# 3_-_IO_Socket_1.net
KiCad netlist of a schematic drawn in Altium Designer
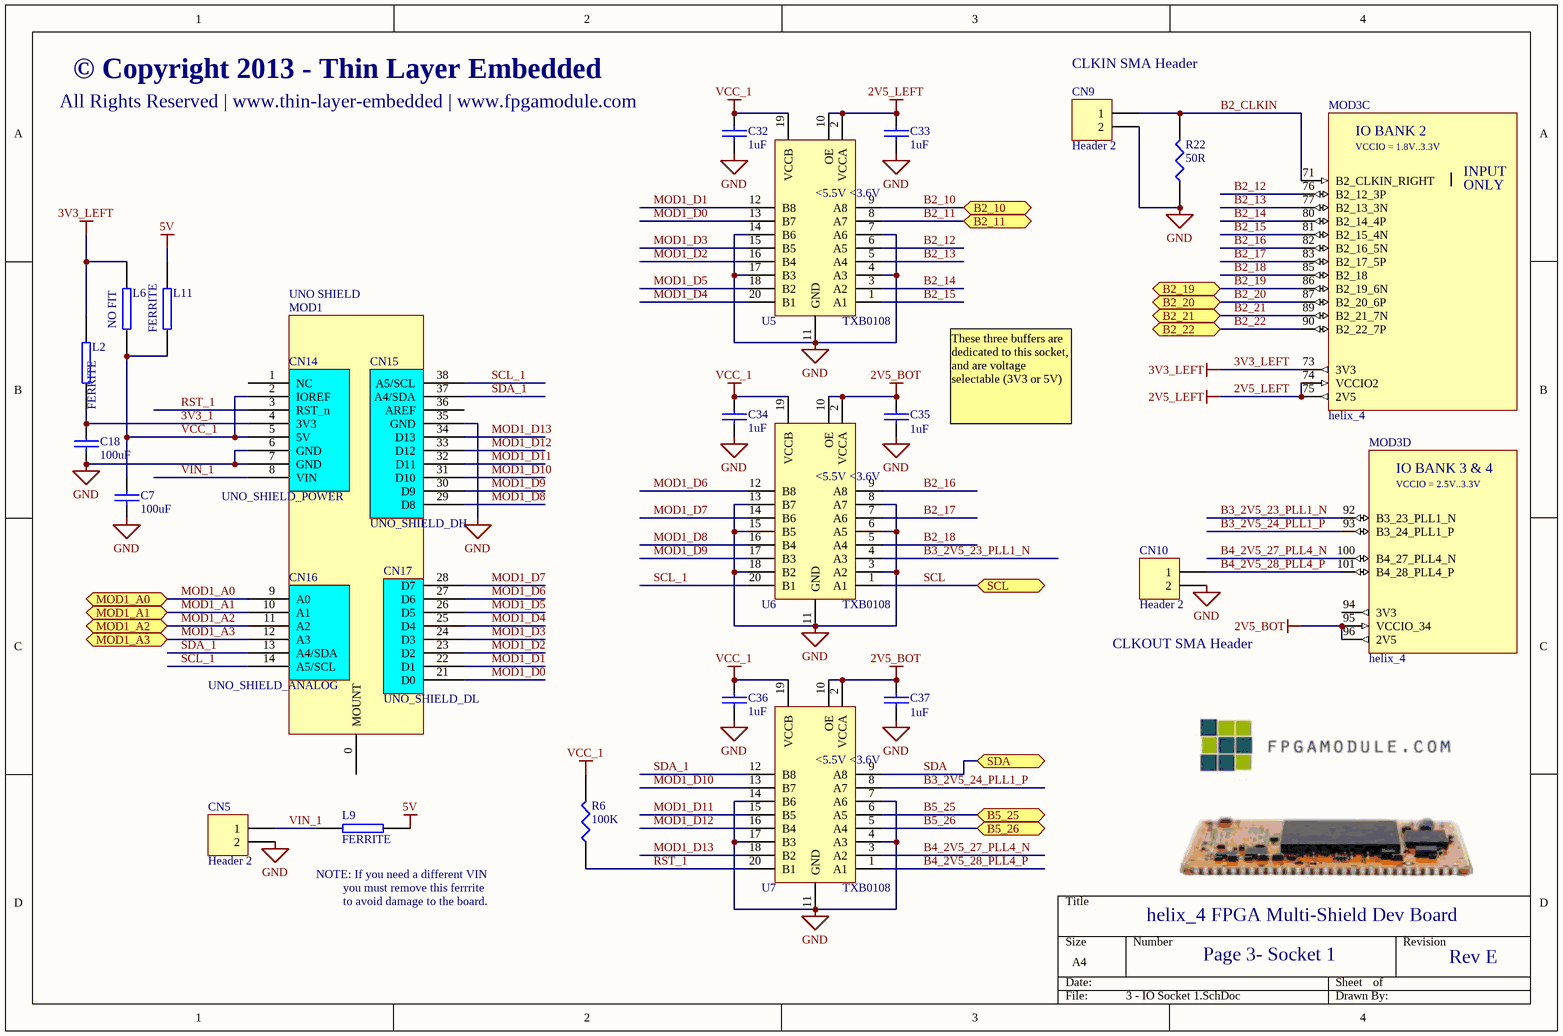
[diagram p0: 3 - IO Socket 1.SchDoc]

(export (version "E")
  (design (tool "Eeschema 10.0.6"))
  (components
    (comp (ref "C7")
      (value "100uF")
      (footprint "1210")
      (description "Capacitor")
      (libsource (lib "*") (part "CAP"))
    )
    (comp (ref "C18")
      (value "100uF")
      (footprint "1210")
      (description "Capacitor")
      (libsource (lib "*") (part "CAP"))
    )
    (comp (ref "C32")
      (value "1uF")
      (footprint "0805")
      (description "Capacitor")
      (libsource (lib "*") (part "CAP"))
    )
    (comp (ref "C33")
      (value "1uF")
      (footprint "0805")
      (description "Capacitor")
      (libsource (lib "*") (part "CAP"))
    )
    (comp (ref "C34")
      (value "1uF")
      (footprint "0805")
      (description "Capacitor")
      (libsource (lib "*") (part "CAP"))
    )
    (comp (ref "C35")
      (value "1uF")
      (footprint "0805")
      (description "Capacitor")
      (libsource (lib "*") (part "CAP"))
    )
    (comp (ref "C36")
      (value "1uF")
      (footprint "0805")
      (description "Capacitor")
      (libsource (lib "*") (part "CAP"))
    )
    (comp (ref "C37")
      (value "1uF")
      (footprint "0805")
      (description "Capacitor")
      (libsource (lib "*") (part "CAP"))
    )
    (comp (ref "CN5")
      (value "Header 2")
      (footprint "HDR1X2")
      (description "Header, 2-Pin")
      (fields (field (name "PUBLISHER") "Altium Limited"))
      (libsource (lib "Miscellaneous Connectors") (part "Header 2"))
    )
    (comp (ref "CN9")
      (value "Header 2")
      (footprint "SMA_V")
      (description "Header, 2-Pin")
      (fields (field (name "PUBLISHER") "Altium Limited"))
      (libsource (lib "Miscellaneous Connectors") (part "Header 2"))
    )
    (comp (ref "CN10")
      (value "Header 2")
      (footprint "SMA_V")
      (description "Header, 2-Pin")
      (fields (field (name "PUBLISHER") "Altium Limited"))
      (libsource (lib "Miscellaneous Connectors") (part "Header 2"))
    )
    (comp (ref "CN14")
      (value "UNO_SHIELD_POWER")
      (footprint "UNO_SHIELD_POWER")
      (libsource (lib "master_library") (part "UNO_SHIELD_POWER"))
    )
    (comp (ref "CN15")
      (value "UNO_SHIELD_DH")
      (footprint "UNO_SHIELD_DH")
      (libsource (lib "master_library") (part "UNO_SHIELD_DH"))
    )
    (comp (ref "CN16")
      (value "UNO_SHIELD_ANALOG")
      (footprint "UNO_SHIELD_ANALOG")
      (libsource (lib "master_library") (part "UNO_SHIELD_ANALOG"))
    )
    (comp (ref "CN17")
      (value "UNO_SHIELD_DL")
      (footprint "UNO_SHIELD_DL")
      (libsource (lib "master_library") (part "UNO_SHIELD_DL"))
    )
    (comp (ref "L2") (value "FERRITE") (footprint "0805") (libsource (lib "*") (part "FERRITE")))
    (comp (ref "L6")
      (value "NO FIT")
      (footprint "0805")
      (description "FERRITE")
      (libsource (lib "*") (part "FERRITE"))
    )
    (comp (ref "L9") (value "FERRITE") (footprint "0805") (libsource (lib "*") (part "FERRITE")))
    (comp (ref "L11") (value "FERRITE") (footprint "0805") (libsource (lib "*") (part "FERRITE")))
    (comp (ref "MOD1")
      (value "UNO SHIELD")
      (footprint "UNO_SHIELD_MECH")
      (libsource (lib "master_library") (part "UNO_SHIELD_MECH"))
    )
    (comp (ref "MOD3")
      (value "helix_4")
      (footprint "HELIX_4_LCC104_HOST")
      (libsource (lib "master_library") (part "helix_4 Rev C Module"))
    )
    (comp (ref "R6") (value "100K") (footprint "0805") (libsource (lib "*") (part "RES1")))
    (comp (ref "R22") (value "50R") (footprint "0805") (libsource (lib "*") (part "RES1")))
    (comp (ref "U5")
      (value "TXB0108")
      (footprint "TSSOP20")
      (description "TI Bir-dir buffer")
      (libsource (lib "master_library") (part "TXB0108"))
    )
    (comp (ref "U6")
      (value "TXB0108")
      (footprint "TSSOP20")
      (description "TI Bir-dir buffer")
      (libsource (lib "master_library") (part "TXB0108"))
    )
    (comp (ref "U7")
      (value "TXB0108")
      (footprint "TSSOP20")
      (description "TI Bir-dir buffer")
      (libsource (lib "master_library") (part "TXB0108"))
    )
  )
  (nets
    (net (code "1") (name "/3V3_1") (class "Default")
      (node (ref "C18") (pin "1") (pinfunction "1_1") (pintype "passive"))
      (node (ref "CN14") (pin "4") (pinfunction "3V3_4") (pintype "passive"))
      (node (ref "L2") (pin "2") (pinfunction "2_2") (pintype "passive"))
    )
    (net (code "2") (name "/B2_10") (class "Default")
      (node (ref "U5") (pin "9") (pinfunction "A8_9") (pintype "passive"))
    )
    (net (code "3") (name "/B2_11") (class "Default")
      (node (ref "U5") (pin "8") (pinfunction "A7_8") (pintype "passive"))
    )
    (net (code "4") (name "/B2_12") (class "Default")
      (node (ref "MOD3") (pin "76") (pinfunction "B2_12_3P_76") (pintype "bidirectional"))
      (node (ref "U5") (pin "6") (pinfunction "A5_6") (pintype "passive"))
    )
    (net (code "5") (name "/B2_13") (class "Default")
      (node (ref "MOD3") (pin "77") (pinfunction "B2_13_3N_77") (pintype "bidirectional"))
      (node (ref "U5") (pin "5") (pinfunction "A4_5") (pintype "passive"))
    )
    (net (code "6") (name "/B2_14") (class "Default")
      (node (ref "MOD3") (pin "80") (pinfunction "B2_14_4P_80") (pintype "bidirectional"))
      (node (ref "U5") (pin "3") (pinfunction "A2_3") (pintype "passive"))
    )
    (net (code "7") (name "/B2_15") (class "Default")
      (node (ref "MOD3") (pin "81") (pinfunction "B2_15_4N_81") (pintype "bidirectional"))
      (node (ref "U5") (pin "1") (pinfunction "A1_1") (pintype "passive"))
    )
    (net (code "8") (name "/B2_16") (class "Default")
      (node (ref "MOD3") (pin "82") (pinfunction "B2_16_5N_82") (pintype "bidirectional"))
      (node (ref "U6") (pin "9") (pinfunction "A8_9") (pintype "passive"))
    )
    (net (code "9") (name "/B2_17") (class "Default")
      (node (ref "MOD3") (pin "83") (pinfunction "B2_17_5P_83") (pintype "bidirectional"))
      (node (ref "U6") (pin "7") (pinfunction "A6_7") (pintype "passive"))
    )
    (net (code "10") (name "/B2_18") (class "Default")
      (node (ref "MOD3") (pin "85") (pinfunction "B2_18_85") (pintype "bidirectional"))
      (node (ref "U6") (pin "5") (pinfunction "A4_5") (pintype "passive"))
    )
    (net (code "11") (name "/B2_19") (class "Default")
      (node (ref "MOD3") (pin "86") (pinfunction "B2_19_6N_86") (pintype "bidirectional"))
    )
    (net (code "12") (name "/B2_20") (class "Default")
      (node (ref "MOD3") (pin "87") (pinfunction "B2_20_6P_87") (pintype "bidirectional"))
    )
    (net (code "13") (name "/B2_21") (class "Default")
      (node (ref "MOD3") (pin "89") (pinfunction "B2_21_7N_89") (pintype "bidirectional"))
    )
    (net (code "14") (name "/B2_22") (class "Default")
      (node (ref "MOD3") (pin "90") (pinfunction "B2_22_7P_90") (pintype "bidirectional"))
    )
    (net (code "15") (name "/B2_CLKIN") (class "Default")
      (node (ref "CN9") (pin "1") (pinfunction "1_1") (pintype "passive"))
      (node (ref "MOD3") (pin "71") (pinfunction "B2_CLKIN_RIGHT_71") (pintype "input"))
      (node (ref "R22") (pin "2") (pinfunction "2_2") (pintype "passive"))
    )
    (net (code "16") (name "/B3_2V5_23_PLL1_N") (class "Default")
      (node (ref "MOD3") (pin "92") (pinfunction "B3_23_PLL1_N_92") (pintype "bidirectional"))
      (node (ref "U6") (pin "4") (pinfunction "A3_4") (pintype "passive"))
    )
    (net (code "17") (name "/B3_2V5_24_PLL1_P") (class "Default")
      (node (ref "MOD3") (pin "93") (pinfunction "B3_24_PLL1_P_93") (pintype "bidirectional"))
      (node (ref "U7") (pin "8") (pinfunction "A7_8") (pintype "passive"))
    )
    (net (code "18") (name "/B4_2V5_27_PLL4_N") (class "Default")
      (node (ref "MOD3") (pin "100") (pinfunction "B4_27_PLL4_N_100") (pintype "bidirectional"))
      (node (ref "U7") (pin "3") (pinfunction "A2_3") (pintype "passive"))
    )
    (net (code "19") (name "/B4_2V5_28_PLL4_P") (class "Default")
      (node (ref "CN10") (pin "1") (pinfunction "1_1") (pintype "passive"))
      (node (ref "MOD3") (pin "101") (pinfunction "B4_28_PLL4_P_101") (pintype "bidirectional"))
      (node (ref "U7") (pin "1") (pinfunction "A1_1") (pintype "passive"))
    )
    (net (code "20") (name "/B5_25") (class "Default")
      (node (ref "U7") (pin "6") (pinfunction "A5_6") (pintype "passive"))
    )
    (net (code "21") (name "/B5_26") (class "Default")
      (node (ref "U7") (pin "5") (pinfunction "A4_5") (pintype "passive"))
    )
    (net (code "22") (name "/MOD1_A0") (class "Default")
      (node (ref "CN16") (pin "9") (pinfunction "A0_9") (pintype "passive"))
    )
    (net (code "23") (name "/MOD1_A1") (class "Default")
      (node (ref "CN16") (pin "10") (pinfunction "A1_10") (pintype "passive"))
    )
    (net (code "24") (name "/MOD1_A2") (class "Default")
      (node (ref "CN16") (pin "11") (pinfunction "A2_11") (pintype "passive"))
    )
    (net (code "25") (name "/MOD1_A3") (class "Default")
      (node (ref "CN16") (pin "12") (pinfunction "A3_12") (pintype "passive"))
    )
    (net (code "26") (name "/MOD1_D0") (class "Default")
      (node (ref "CN17") (pin "21") (pinfunction "D0_21") (pintype "passive"))
      (node (ref "U5") (pin "13") (pinfunction "B7_13") (pintype "passive"))
    )
    (net (code "27") (name "/MOD1_D1") (class "Default")
      (node (ref "CN17") (pin "22") (pinfunction "D1_22") (pintype "passive"))
      (node (ref "U5") (pin "12") (pinfunction "B8_12") (pintype "passive"))
    )
    (net (code "28") (name "/MOD1_D2") (class "Default")
      (node (ref "CN17") (pin "23") (pinfunction "D2_23") (pintype "passive"))
      (node (ref "U5") (pin "16") (pinfunction "B4_16") (pintype "passive"))
    )
    (net (code "29") (name "/MOD1_D3") (class "Default")
      (node (ref "CN17") (pin "24") (pinfunction "D3_24") (pintype "passive"))
      (node (ref "U5") (pin "15") (pinfunction "B5_15") (pintype "passive"))
    )
    (net (code "30") (name "/MOD1_D4") (class "Default")
      (node (ref "CN17") (pin "25") (pinfunction "D4_25") (pintype "passive"))
      (node (ref "U5") (pin "20") (pinfunction "B1_20") (pintype "passive"))
    )
    (net (code "31") (name "/MOD1_D5") (class "Default")
      (node (ref "CN17") (pin "26") (pinfunction "D5_26") (pintype "passive"))
      (node (ref "U5") (pin "18") (pinfunction "B2_18") (pintype "passive"))
    )
    (net (code "32") (name "/MOD1_D6") (class "Default")
      (node (ref "CN17") (pin "27") (pinfunction "D6_27") (pintype "passive"))
      (node (ref "U6") (pin "12") (pinfunction "B8_12") (pintype "passive"))
    )
    (net (code "33") (name "/MOD1_D7") (class "Default")
      (node (ref "CN17") (pin "28") (pinfunction "D7_28") (pintype "passive"))
      (node (ref "U6") (pin "14") (pinfunction "B6_14") (pintype "passive"))
    )
    (net (code "34") (name "/MOD1_D8") (class "Default")
      (node (ref "CN15") (pin "29") (pinfunction "D8_29") (pintype "passive"))
      (node (ref "U6") (pin "16") (pinfunction "B4_16") (pintype "passive"))
    )
    (net (code "35") (name "/MOD1_D9") (class "Default")
      (node (ref "CN15") (pin "30") (pinfunction "D9_30") (pintype "passive"))
      (node (ref "U6") (pin "17") (pinfunction "B3_17") (pintype "passive"))
    )
    (net (code "36") (name "/MOD1_D10") (class "Default")
      (node (ref "CN15") (pin "31") (pinfunction "D10_31") (pintype "passive"))
      (node (ref "U7") (pin "13") (pinfunction "B7_13") (pintype "passive"))
    )
    (net (code "37") (name "/MOD1_D11") (class "Default")
      (node (ref "CN15") (pin "32") (pinfunction "D11_32") (pintype "passive"))
      (node (ref "U7") (pin "15") (pinfunction "B5_15") (pintype "passive"))
    )
    (net (code "38") (name "/MOD1_D12") (class "Default")
      (node (ref "CN15") (pin "33") (pinfunction "D12_33") (pintype "passive"))
      (node (ref "U7") (pin "16") (pinfunction "B4_16") (pintype "passive"))
    )
    (net (code "39") (name "/MOD1_D13") (class "Default")
      (node (ref "CN15") (pin "34") (pinfunction "D13_34") (pintype "passive"))
      (node (ref "U7") (pin "18") (pinfunction "B2_18") (pintype "passive"))
    )
    (net (code "40") (name "/RST_1") (class "Default")
      (node (ref "CN14") (pin "3") (pinfunction "RST_n_3") (pintype "passive"))
      (node (ref "R6") (pin "1") (pinfunction "1_1") (pintype "passive"))
      (node (ref "U7") (pin "20") (pinfunction "B1_20") (pintype "passive"))
    )
    (net (code "41") (name "/SCL") (class "Default")
      (node (ref "U6") (pin "1") (pinfunction "A1_1") (pintype "passive"))
    )
    (net (code "42") (name "/SCL_1") (class "Default")
      (node (ref "CN15") (pin "38") (pinfunction "A5/SCL_38") (pintype "passive"))
      (node (ref "CN16") (pin "14") (pinfunction "A5/SCL_14") (pintype "passive"))
      (node (ref "U6") (pin "20") (pinfunction "B1_20") (pintype "passive"))
    )
    (net (code "43") (name "/SDA") (class "Default")
      (node (ref "U7") (pin "9") (pinfunction "A8_9") (pintype "passive"))
    )
    (net (code "44") (name "/SDA_1") (class "Default")
      (node (ref "CN15") (pin "37") (pinfunction "A4/SDA_37") (pintype "passive"))
      (node (ref "CN16") (pin "13") (pinfunction "A4/SDA_13") (pintype "passive"))
      (node (ref "U7") (pin "12") (pinfunction "B8_12") (pintype "passive"))
    )
    (net (code "45") (name "/VIN_1") (class "Default")
      (node (ref "CN14") (pin "8") (pinfunction "VIN_8") (pintype "passive"))
      (node (ref "CN5") (pin "1") (pinfunction "1_1") (pintype "passive"))
      (node (ref "L9") (pin "2") (pinfunction "2_2") (pintype "passive"))
    )
    (net (code "46") (name "2V5_BOT") (class "Default")
      (node (ref "C35") (pin "2") (pinfunction "2_2") (pintype "passive"))
      (node (ref "C37") (pin "2") (pinfunction "2_2") (pintype "passive"))
      (node (ref "MOD3") (pin "95") (pinfunction "VCCIO_34_95") (pintype "input"))
      (node (ref "MOD3") (pin "96") (pinfunction "2V5_96") (pintype "output"))
      (node (ref "U6") (pin "10") (pinfunction "OE_10") (pintype "passive"))
      (node (ref "U6") (pin "2") (pinfunction "VCCA_2") (pintype "passive"))
      (node (ref "U7") (pin "10") (pinfunction "OE_10") (pintype "passive"))
      (node (ref "U7") (pin "2") (pinfunction "VCCA_2") (pintype "passive"))
    )
    (net (code "47") (name "2V5_LEFT") (class "Default")
      (node (ref "C33") (pin "2") (pinfunction "2_2") (pintype "passive"))
      (node (ref "MOD3") (pin "74") (pinfunction "VCCIO2_74") (pintype "input"))
      (node (ref "MOD3") (pin "75") (pinfunction "2V5_75") (pintype "output"))
      (node (ref "U5") (pin "10") (pinfunction "OE_10") (pintype "passive"))
      (node (ref "U5") (pin "2") (pinfunction "VCCA_2") (pintype "passive"))
    )
    (net (code "48") (name "3V3_LEFT") (class "Default")
      (node (ref "L2") (pin "1") (pinfunction "1_1") (pintype "passive"))
      (node (ref "L6") (pin "1") (pinfunction "1_1") (pintype "passive"))
      (node (ref "MOD3") (pin "73") (pinfunction "3V3_73") (pintype "output"))
    )
    (net (code "49") (name "5V") (class "Default")
      (node (ref "L11") (pin "1") (pinfunction "1_1") (pintype "passive"))
      (node (ref "L9") (pin "1") (pinfunction "1_1") (pintype "passive"))
    )
    (net (code "50") (name "GND") (class "Default")
      (node (ref "C18") (pin "2") (pinfunction "2_2") (pintype "passive"))
      (node (ref "C32") (pin "1") (pinfunction "1_1") (pintype "passive"))
      (node (ref "C33") (pin "1") (pinfunction "1_1") (pintype "passive"))
      (node (ref "C34") (pin "1") (pinfunction "1_1") (pintype "passive"))
      (node (ref "C35") (pin "1") (pinfunction "1_1") (pintype "passive"))
      (node (ref "C36") (pin "1") (pinfunction "1_1") (pintype "passive"))
      (node (ref "C37") (pin "1") (pinfunction "1_1") (pintype "passive"))
      (node (ref "C7") (pin "2") (pinfunction "2_2") (pintype "passive"))
      (node (ref "CN10") (pin "2") (pinfunction "2_2") (pintype "passive"))
      (node (ref "CN14") (pin "6") (pinfunction "GND_6") (pintype "passive"))
      (node (ref "CN14") (pin "7") (pinfunction "GND_7") (pintype "passive"))
      (node (ref "CN15") (pin "35") (pinfunction "GND_35") (pintype "passive"))
      (node (ref "CN5") (pin "2") (pinfunction "2_2") (pintype "passive"))
      (node (ref "CN9") (pin "2") (pinfunction "2_2") (pintype "passive"))
      (node (ref "R22") (pin "1") (pinfunction "1_1") (pintype "passive"))
      (node (ref "U5") (pin "11") (pinfunction "GND_11") (pintype "passive"))
      (node (ref "U5") (pin "14") (pinfunction "B6_14") (pintype "passive"))
      (node (ref "U5") (pin "17") (pinfunction "B3_17") (pintype "passive"))
      (node (ref "U5") (pin "4") (pinfunction "A3_4") (pintype "passive"))
      (node (ref "U5") (pin "7") (pinfunction "A6_7") (pintype "passive"))
      (node (ref "U6") (pin "11") (pinfunction "GND_11") (pintype "passive"))
      (node (ref "U6") (pin "13") (pinfunction "B7_13") (pintype "passive"))
      (node (ref "U6") (pin "15") (pinfunction "B5_15") (pintype "passive"))
      (node (ref "U6") (pin "18") (pinfunction "B2_18") (pintype "passive"))
      (node (ref "U6") (pin "3") (pinfunction "A2_3") (pintype "passive"))
      (node (ref "U6") (pin "6") (pinfunction "A5_6") (pintype "passive"))
      (node (ref "U6") (pin "8") (pinfunction "A7_8") (pintype "passive"))
      (node (ref "U7") (pin "11") (pinfunction "GND_11") (pintype "passive"))
      (node (ref "U7") (pin "14") (pinfunction "B6_14") (pintype "passive"))
      (node (ref "U7") (pin "17") (pinfunction "B3_17") (pintype "passive"))
      (node (ref "U7") (pin "4") (pinfunction "A3_4") (pintype "passive"))
      (node (ref "U7") (pin "7") (pinfunction "A6_7") (pintype "passive"))
    )
    (net (code "51") (name "VCC_1") (class "Default")
      (node (ref "C32") (pin "2") (pinfunction "2_2") (pintype "passive"))
      (node (ref "C34") (pin "2") (pinfunction "2_2") (pintype "passive"))
      (node (ref "C36") (pin "2") (pinfunction "2_2") (pintype "passive"))
      (node (ref "C7") (pin "1") (pinfunction "1_1") (pintype "passive"))
      (node (ref "CN14") (pin "2") (pinfunction "IOREF_2") (pintype "passive"))
      (node (ref "CN14") (pin "5") (pinfunction "5V_5") (pintype "passive"))
      (node (ref "L11") (pin "2") (pinfunction "2_2") (pintype "passive"))
      (node (ref "L6") (pin "2") (pinfunction "2_2") (pintype "passive"))
      (node (ref "R6") (pin "2") (pinfunction "2_2") (pintype "passive"))
      (node (ref "U5") (pin "19") (pinfunction "VCCB_19") (pintype "passive"))
      (node (ref "U6") (pin "19") (pinfunction "VCCB_19") (pintype "passive"))
      (node (ref "U7") (pin "19") (pinfunction "VCCB_19") (pintype "passive"))
    )
    (net (code "52") (name "unconnected-(CN14-NC-Pad1)") (class "Default")
      (node (ref "CN14") (pin "1") (pinfunction "NC_1") (pintype "passive"))
    )
    (net (code "53") (name "unconnected-(CN15-AREF-Pad36)") (class "Default")
      (node (ref "CN15") (pin "36") (pinfunction "AREF_36") (pintype "passive"))
    )
    (net (code "54") (name "unconnected-(MOD1-MOUNT-Pad0)") (class "Default")
      (node (ref "MOD1") (pin "0") (pinfunction "MOUNT_0") (pintype "passive"))
    )
    (net (code "55") (name "unconnected-(MOD3D-3V3-Pad94)") (class "Default")
      (node (ref "MOD3") (pin "94") (pinfunction "3V3_94") (pintype "output"))
    )
  )
)
